# ValvePCB_V4_Edit_17-09-2023.net
KiCad netlist of a schematic drawn in EAGLE
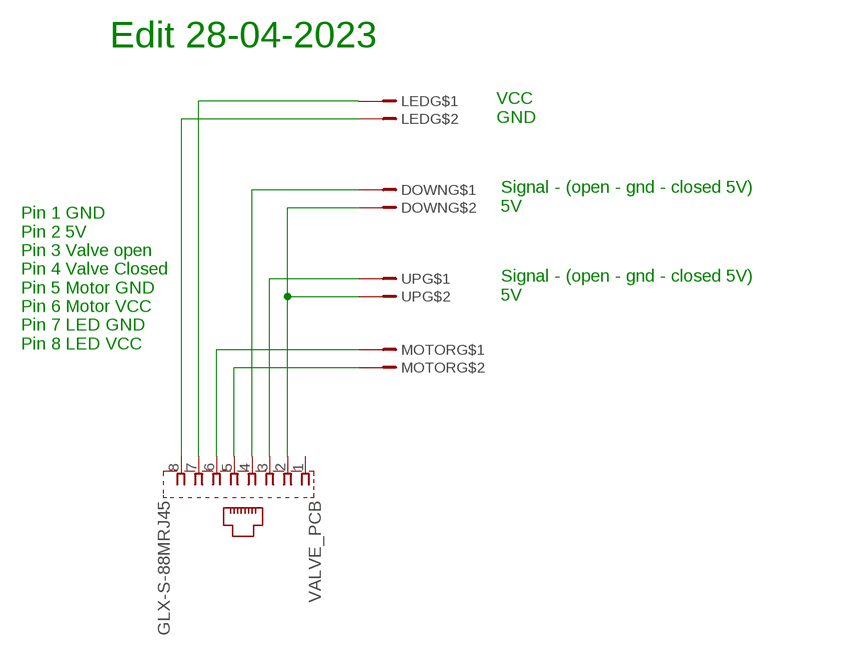
[diagram p0: schematic, sheet 1]

(export (version "E")
  (design (tool "Eeschema 10.0.6"))
  (components
    (comp (ref "DOWN")
      (value "JST2")
      (footprint "eagle-import:HDRV2W64P254_1X2_712X508X838B")
      (libsource (lib "eagle-import") (part "JST2"))
    )
    (comp (ref "LED")
      (value "JST2")
      (footprint "eagle-import:HDRV2W64P254_1X2_712X508X838B")
      (libsource (lib "eagle-import") (part "JST2"))
    )
    (comp (ref "MOTOR")
      (value "JST2")
      (footprint "eagle-import:HDRV2W64P254_1X2_712X508X838B")
      (libsource (lib "eagle-import") (part "JST2"))
    )
    (comp (ref "UP")
      (value "JST2")
      (footprint "eagle-import:HDRV2W64P254_1X2_712X508X838B")
      (libsource (lib "eagle-import") (part "JST2"))
    )
    (comp (ref "VALVE_PCB")
      (value "GLX-S-88MRJ45")
      (footprint "eagle-import:GLX-S-88M")
      (libsource (lib "eagle-import") (part "GLX-S-88MRJ45"))
    )
  )
  (nets
    (net (code "1") (name "Net-(DOWN-Pad1)") (class "Default")
      (node (ref "DOWN") (pin "1") (pinfunction "1_1") (pintype "passive"))
      (node (ref "VALVE_PCB") (pin "4") (pinfunction "4_4") (pintype "passive"))
    )
    (net (code "2") (name "Net-(DOWNB-1)") (class "Default")
      (node (ref "DOWN") (pin "2") (pinfunction "1_2") (pintype "passive"))
      (node (ref "UP") (pin "2") (pinfunction "1_2") (pintype "passive"))
      (node (ref "VALVE_PCB") (pin "2") (pinfunction "2_2") (pintype "passive"))
    )
    (net (code "3") (name "Net-(LED-Pad1)") (class "Default")
      (node (ref "LED") (pin "1") (pinfunction "1_1") (pintype "passive"))
      (node (ref "VALVE_PCB") (pin "7") (pinfunction "7_7") (pintype "passive"))
    )
    (net (code "4") (name "Net-(LEDB-1)") (class "Default")
      (node (ref "LED") (pin "2") (pinfunction "1_2") (pintype "passive"))
      (node (ref "VALVE_PCB") (pin "8") (pinfunction "8_8") (pintype "passive"))
    )
    (net (code "5") (name "Net-(MOTOR-Pad1)") (class "Default")
      (node (ref "MOTOR") (pin "1") (pinfunction "1_1") (pintype "passive"))
      (node (ref "VALVE_PCB") (pin "6") (pinfunction "6_6") (pintype "passive"))
    )
    (net (code "6") (name "Net-(MOTORB-1)") (class "Default")
      (node (ref "MOTOR") (pin "2") (pinfunction "1_2") (pintype "passive"))
      (node (ref "VALVE_PCB") (pin "5") (pinfunction "5_5") (pintype "passive"))
    )
    (net (code "7") (name "Net-(UP-Pad1)") (class "Default")
      (node (ref "UP") (pin "1") (pinfunction "1_1") (pintype "passive"))
      (node (ref "VALVE_PCB") (pin "3") (pinfunction "3_3") (pintype "passive"))
    )
    (net (code "8") (name "unconnected-(VALVE_PCB-Pad1)") (class "Default")
      (node (ref "VALVE_PCB") (pin "1") (pinfunction "1_1") (pintype "passive"))
    )
  )
)
